# ProPrj_ExtModule-001_2024-08-27.net
KiCad netlist of a schematic drawn in EasyEDA Pro
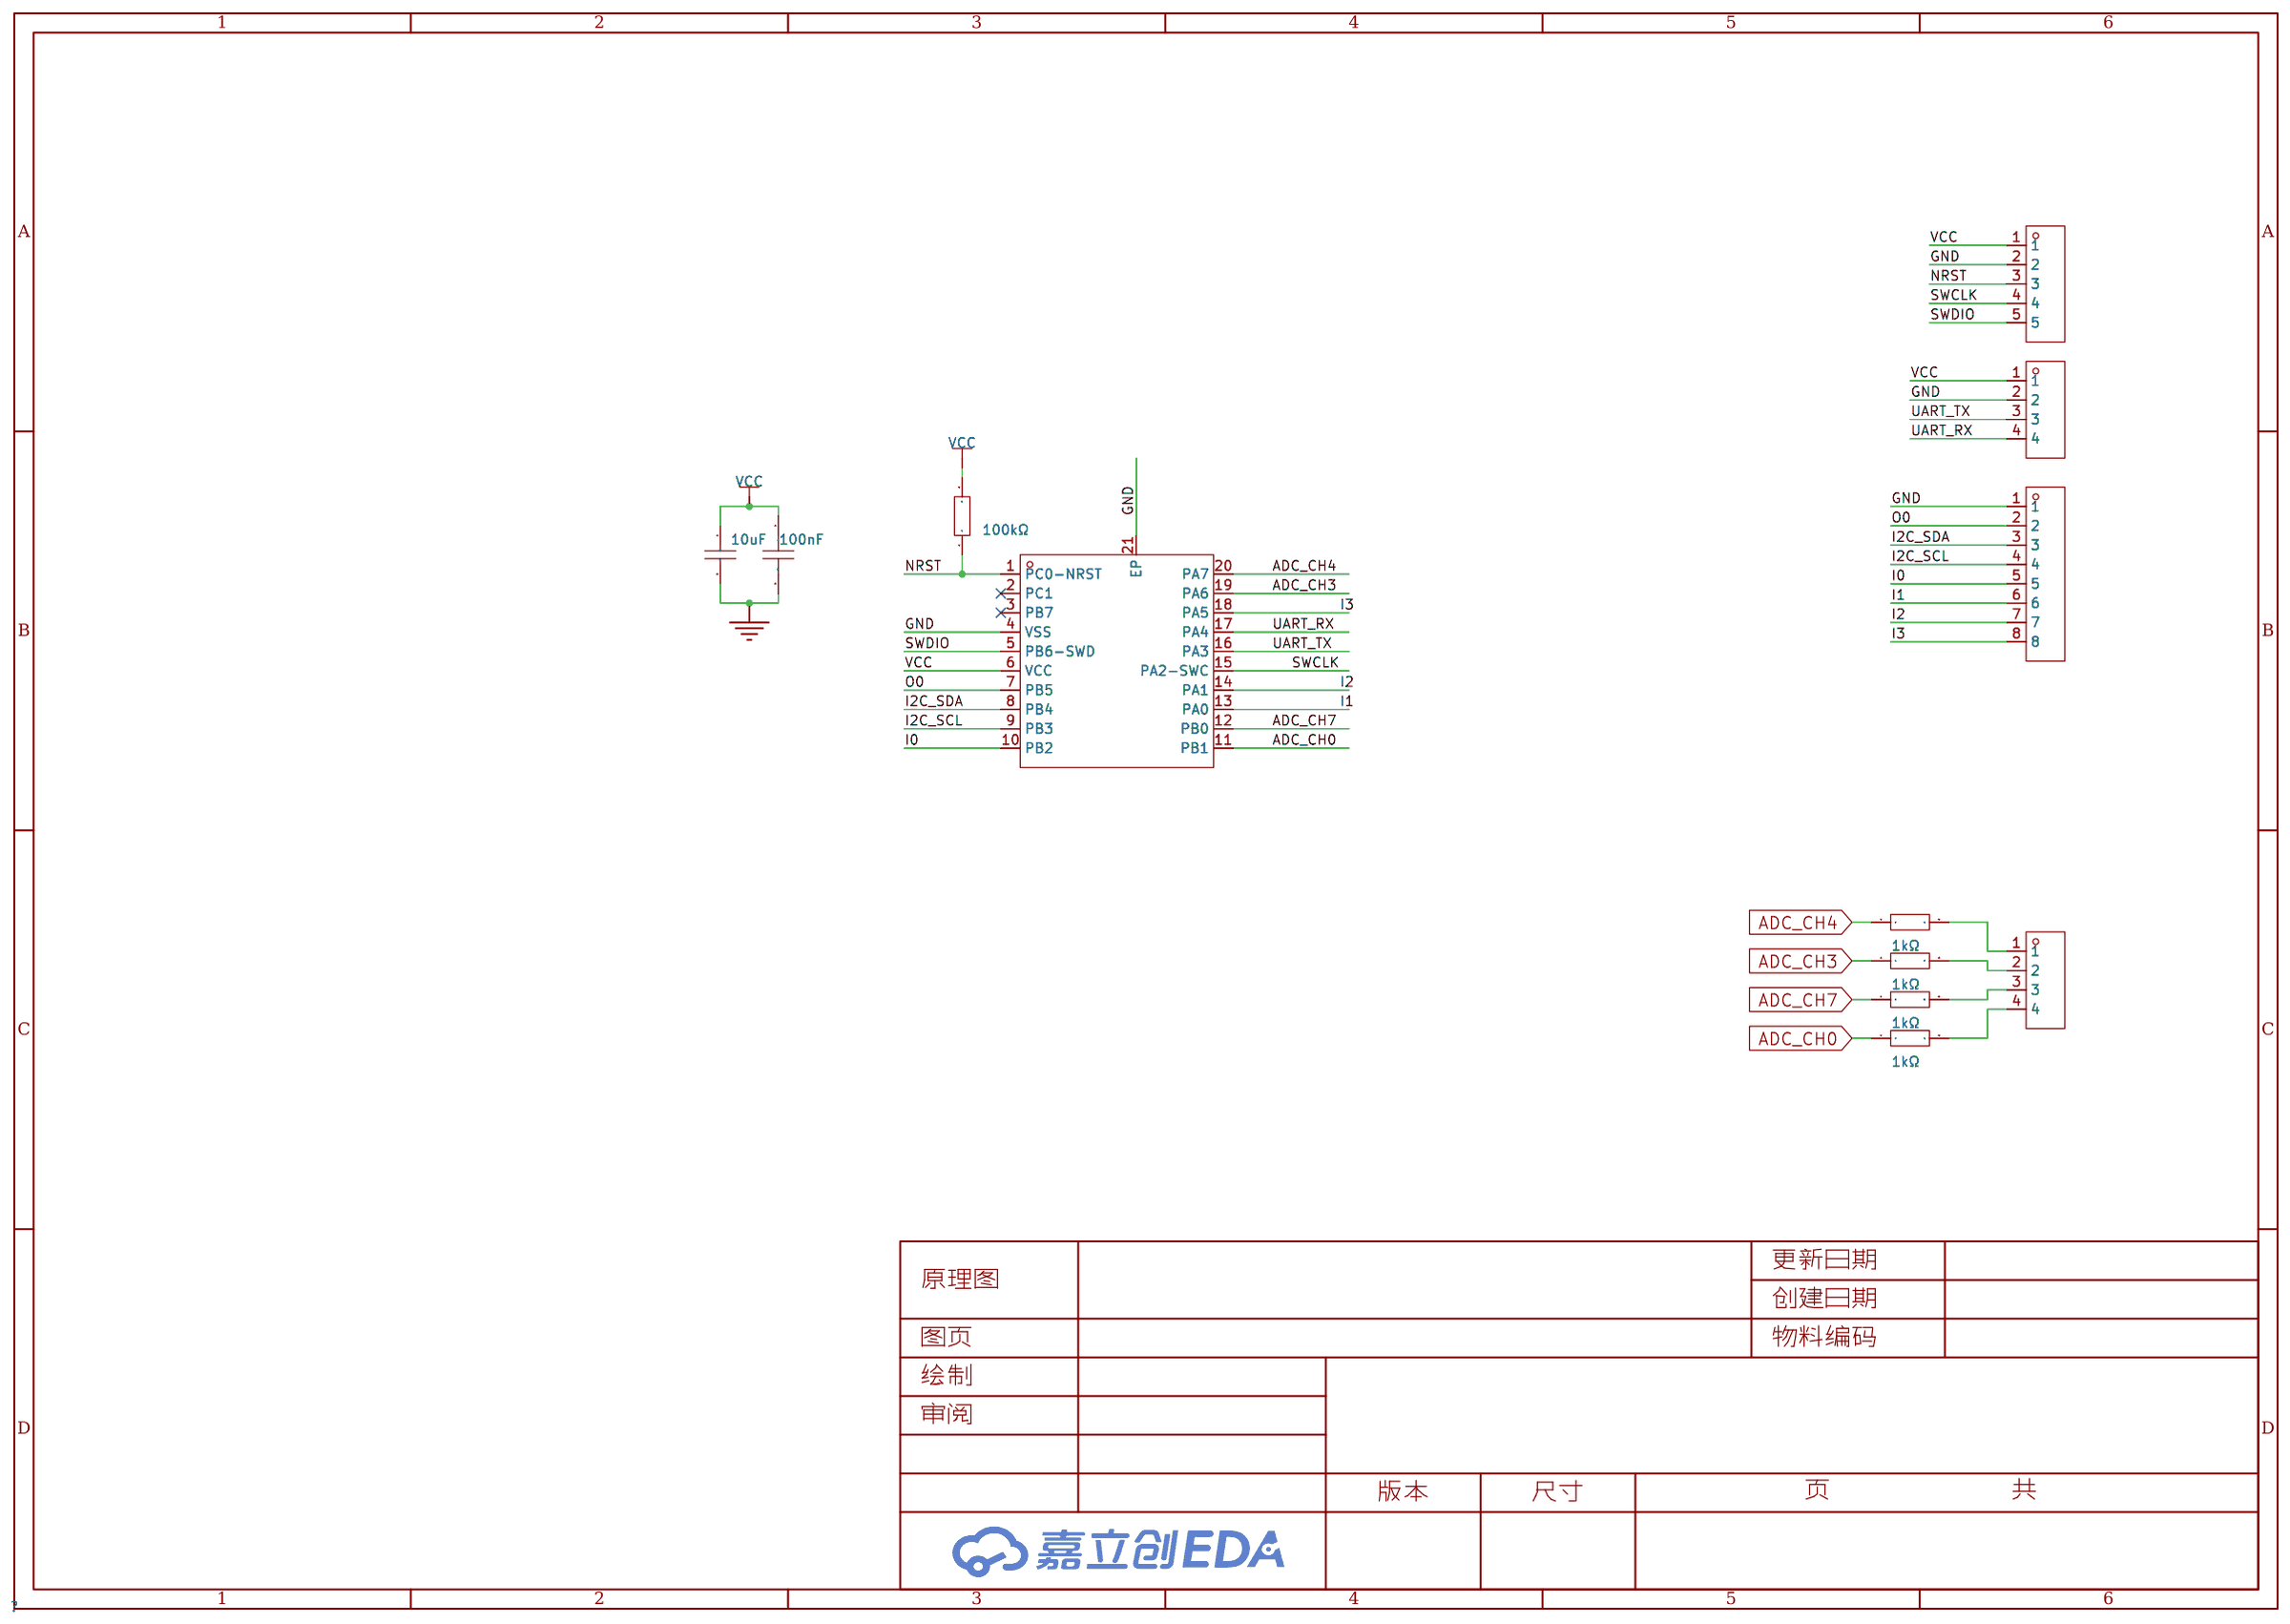
[diagram p0: schematic sheet]

(export (version "E")
  (design (tool "Eeschema 10.0.6"))
  (components
    (comp (ref "C3")
      (value "100nF")
      (footprint "easyedapro:C0402")
      (description "容值:100nF;精度:±10%;额定电压:16V;材质(温度系数):X7R;")
      (fields
        (field (name "Manufacturer Part") "CC0402KRX7R7BB104")
        (field (name "Manufacturer") "YAGEO(国巨)")
      )
      (libsource (lib "easyedapro") (part "CC0402KRX7R7BB104"))
    )
    (comp (ref "C4")
      (value "10uF")
      (footprint "easyedapro:C0402")
      (description "容值:10uF;精度:±20%;额定电压:6.3V;材质(温度系数):X5R;")
      (fields
        (field (name "Manufacturer Part") "CL05A106MQ5NUNC")
        (field (name "Manufacturer") "SAMSUNG(三星)")
      )
      (libsource (lib "easyedapro") (part "CL05A106MQ5NUNC"))
    )
    (comp (ref "CN1")
      (value "HC-PZ254-11.5L-1x5PZ")
      (footprint "easyedapro:HDR-TH_5P-P2.54-V-M")
      (fields (field (name "Manufacturer") "HC(虹成电子)"))
      (libsource (lib "easyedapro") (part "HC-PZ254-11.5L-1X5PZ"))
    )
    (comp (ref "H1")
      (value "PZ254V-11-04P")
      (footprint "easyedapro:HDR-TH_4P-P2.54-V-M")
      (fields (field (name "Manufacturer") "XFCN(兴飞)"))
      (libsource (lib "easyedapro") (part "PZ254V-11-04P_C2691448"))
    )
    (comp (ref "H2")
      (value "PZ254V-11-08P")
      (footprint "easyedapro:HDR-TH_8P-P2.54-V-M")
      (fields (field (name "Manufacturer") "XFCN(兴飞)"))
      (libsource (lib "easyedapro") (part "PZ254V-11-08P"))
    )
    (comp (ref "H3")
      (value "PZ254V-11-04P")
      (footprint "easyedapro:HDR-TH_4P-P2.54-V-M")
      (fields (field (name "Manufacturer") "XFCN(兴飞)"))
      (libsource (lib "easyedapro") (part "PZ254V-11-04P_C2691448"))
    )
    (comp (ref "R1")
      (value "100kΩ")
      (footprint "easyedapro:R0402")
      (description "电阻类型:厚膜电阻;阻值:100kΩ;精度:±1%;功率:62.5mW;最大工作电压:50V;温度系数:±100ppm/°C;")
      (fields (field (name "Manufacturer Part") "RC0402FR-07100KL") (field (name "Manufacturer") "YAGEO(国巨)"))
      (libsource (lib "easyedapro") (part "RC0402FR-07100KL"))
    )
    (comp (ref "R2")
      (value "1kΩ")
      (footprint "easyedapro:R0402")
      (description "电阻类型:厚膜电阻;阻值:1kΩ;精度:±1%;功率:62.5mW;最大工作电压:50V;温度系数:±100ppm/°C;")
      (fields (field (name "Manufacturer Part") "RC0402FR-071KL") (field (name "Manufacturer") "YAGEO(国巨)"))
      (libsource (lib "easyedapro") (part "RC0402FR-071KL"))
    )
    (comp (ref "R3")
      (value "1kΩ")
      (footprint "easyedapro:R0402")
      (description "电阻类型:厚膜电阻;阻值:1kΩ;精度:±1%;功率:62.5mW;最大工作电压:50V;温度系数:±100ppm/°C;")
      (fields (field (name "Manufacturer Part") "RC0402FR-071KL") (field (name "Manufacturer") "YAGEO(国巨)"))
      (libsource (lib "easyedapro") (part "RC0402FR-071KL"))
    )
    (comp (ref "R4")
      (value "1kΩ")
      (footprint "easyedapro:R0402")
      (description "电阻类型:厚膜电阻;阻值:1kΩ;精度:±1%;功率:62.5mW;最大工作电压:50V;温度系数:±100ppm/°C;")
      (fields (field (name "Manufacturer Part") "RC0402FR-071KL") (field (name "Manufacturer") "YAGEO(国巨)"))
      (libsource (lib "easyedapro") (part "RC0402FR-071KL"))
    )
    (comp (ref "R5")
      (value "1kΩ")
      (footprint "easyedapro:R0402")
      (description "电阻类型:厚膜电阻;阻值:1kΩ;精度:±1%;功率:62.5mW;最大工作电压:50V;温度系数:±100ppm/°C;")
      (fields (field (name "Manufacturer Part") "RC0402FR-071KL") (field (name "Manufacturer") "YAGEO(国巨)"))
      (libsource (lib "easyedapro") (part "RC0402FR-071KL"))
    )
    (comp (ref "U1")
      (value "2dbf3a06cba34a84b0df513ae8ead8ff")
      (footprint "easyedapro:QFN-20_L3.0-W3.0-P0.40-TL-EP1.7")
      (fields (field (name "Manufacturer Part") "PY32F002BF15U6TR") (field (name "Manufacturer") "PUYA(普冉)"))
      (libsource (lib "easyedapro") (part "PY32F002BF15U6TR"))
    )
  )
  (nets
    (net (code "1") (name "/I0") (class "Default")
      (node (ref "H2") (pin "5") (pinfunction "5_5") (pintype "unspecified"))
      (node (ref "U1") (pin "10") (pinfunction "PB2_10") (pintype "unspecified"))
    )
    (net (code "2") (name "/I1") (class "Default")
      (node (ref "H2") (pin "6") (pinfunction "6_6") (pintype "unspecified"))
      (node (ref "U1") (pin "13") (pinfunction "PA0_13") (pintype "unspecified"))
    )
    (net (code "3") (name "/I2") (class "Default")
      (node (ref "H2") (pin "7") (pinfunction "7_7") (pintype "unspecified"))
      (node (ref "U1") (pin "14") (pinfunction "PA1_14") (pintype "unspecified"))
    )
    (net (code "4") (name "/I2C_SCL") (class "Default")
      (node (ref "H2") (pin "4") (pinfunction "4_4") (pintype "unspecified"))
      (node (ref "U1") (pin "9") (pinfunction "PB3_9") (pintype "unspecified"))
    )
    (net (code "5") (name "/I2C_SDA") (class "Default")
      (node (ref "H2") (pin "3") (pinfunction "3_3") (pintype "unspecified"))
      (node (ref "U1") (pin "8") (pinfunction "PB4_8") (pintype "unspecified"))
    )
    (net (code "6") (name "/I3") (class "Default")
      (node (ref "H2") (pin "8") (pinfunction "8_8") (pintype "unspecified"))
      (node (ref "U1") (pin "18") (pinfunction "PA5_18") (pintype "unspecified"))
    )
    (net (code "7") (name "/NRST") (class "Default")
      (node (ref "CN1") (pin "3") (pinfunction "3_3") (pintype "unspecified"))
      (node (ref "R1") (pin "1") (pinfunction "1_1") (pintype "input"))
      (node (ref "U1") (pin "1") (pinfunction "PC0-NRST_1") (pintype "unspecified"))
    )
    (net (code "8") (name "/O0") (class "Default")
      (node (ref "H2") (pin "2") (pinfunction "2_2") (pintype "unspecified"))
      (node (ref "U1") (pin "7") (pinfunction "PB5_7") (pintype "unspecified"))
    )
    (net (code "9") (name "/SWCLK") (class "Default")
      (node (ref "CN1") (pin "4") (pinfunction "4_4") (pintype "unspecified"))
      (node (ref "U1") (pin "15") (pinfunction "PA2-SWC_15") (pintype "unspecified"))
    )
    (net (code "10") (name "/SWDIO") (class "Default")
      (node (ref "CN1") (pin "5") (pinfunction "5_5") (pintype "unspecified"))
      (node (ref "U1") (pin "5") (pinfunction "PB6-SWD_5") (pintype "unspecified"))
    )
    (net (code "11") (name "/UART_RX") (class "Default")
      (node (ref "H1") (pin "4") (pinfunction "4_4") (pintype "unspecified"))
      (node (ref "U1") (pin "17") (pinfunction "PA4_17") (pintype "unspecified"))
    )
    (net (code "12") (name "/UART_TX") (class "Default")
      (node (ref "H1") (pin "3") (pinfunction "3_3") (pintype "unspecified"))
      (node (ref "U1") (pin "16") (pinfunction "PA3_16") (pintype "unspecified"))
    )
    (net (code "13") (name "ADC_CH0") (class "Default")
      (node (ref "R5") (pin "1") (pinfunction "1_1") (pintype "input"))
      (node (ref "U1") (pin "11") (pinfunction "PB1_11") (pintype "unspecified"))
    )
    (net (code "14") (name "ADC_CH3") (class "Default")
      (node (ref "R3") (pin "1") (pinfunction "1_1") (pintype "input"))
      (node (ref "U1") (pin "19") (pinfunction "PA6_19") (pintype "unspecified"))
    )
    (net (code "15") (name "ADC_CH4") (class "Default")
      (node (ref "R2") (pin "1") (pinfunction "1_1") (pintype "input"))
      (node (ref "U1") (pin "20") (pinfunction "PA7_20") (pintype "unspecified"))
    )
    (net (code "16") (name "ADC_CH7") (class "Default")
      (node (ref "R4") (pin "1") (pinfunction "1_1") (pintype "input"))
      (node (ref "U1") (pin "12") (pinfunction "PB0_12") (pintype "unspecified"))
    )
    (net (code "17") (name "GND") (class "Default")
      (node (ref "C3") (pin "2") (pinfunction "2_2") (pintype "unspecified"))
      (node (ref "C4") (pin "2") (pinfunction "2_2") (pintype "input"))
      (node (ref "CN1") (pin "2") (pinfunction "2_2") (pintype "unspecified"))
      (node (ref "H1") (pin "2") (pinfunction "2_2") (pintype "unspecified"))
      (node (ref "H2") (pin "1") (pinfunction "1_1") (pintype "unspecified"))
      (node (ref "U1") (pin "21") (pinfunction "EP_21") (pintype "unspecified"))
      (node (ref "U1") (pin "4") (pinfunction "VSS_4") (pintype "unspecified"))
    )
    (net (code "18") (name "Net-(H3-Pad1)") (class "Default")
      (node (ref "H3") (pin "1") (pinfunction "1_1") (pintype "unspecified"))
      (node (ref "R2") (pin "2") (pinfunction "2_2") (pintype "input"))
    )
    (net (code "19") (name "Net-(H3-Pad2)") (class "Default")
      (node (ref "H3") (pin "2") (pinfunction "2_2") (pintype "unspecified"))
      (node (ref "R3") (pin "2") (pinfunction "2_2") (pintype "input"))
    )
    (net (code "20") (name "Net-(H3-Pad3)") (class "Default")
      (node (ref "H3") (pin "3") (pinfunction "3_3") (pintype "unspecified"))
      (node (ref "R4") (pin "2") (pinfunction "2_2") (pintype "input"))
    )
    (net (code "21") (name "Net-(H3-Pad4)") (class "Default")
      (node (ref "H3") (pin "4") (pinfunction "4_4") (pintype "unspecified"))
      (node (ref "R5") (pin "2") (pinfunction "2_2") (pintype "input"))
    )
    (net (code "22") (name "VCC") (class "Default")
      (node (ref "C3") (pin "1") (pinfunction "1_1") (pintype "unspecified"))
      (node (ref "C4") (pin "1") (pinfunction "1_1") (pintype "input"))
      (node (ref "CN1") (pin "1") (pinfunction "1_1") (pintype "unspecified"))
      (node (ref "H1") (pin "1") (pinfunction "1_1") (pintype "unspecified"))
      (node (ref "R1") (pin "2") (pinfunction "2_2") (pintype "input"))
      (node (ref "U1") (pin "6") (pinfunction "VCC_6") (pintype "unspecified"))
    )
    (net (code "23") (name "unconnected-(U1-PB7-Pad3)") (class "Default")
      (node (ref "U1") (pin "3") (pinfunction "PB7_3") (pintype "unspecified+no_connect"))
    )
    (net (code "24") (name "unconnected-(U1-PC1-Pad2)") (class "Default")
      (node (ref "U1") (pin "2") (pinfunction "PC1_2") (pintype "unspecified+no_connect"))
    )
  )
)
